# VFD_alpha_Sheet0.net
KiCad netlist of a schematic drawn in Altium Designer
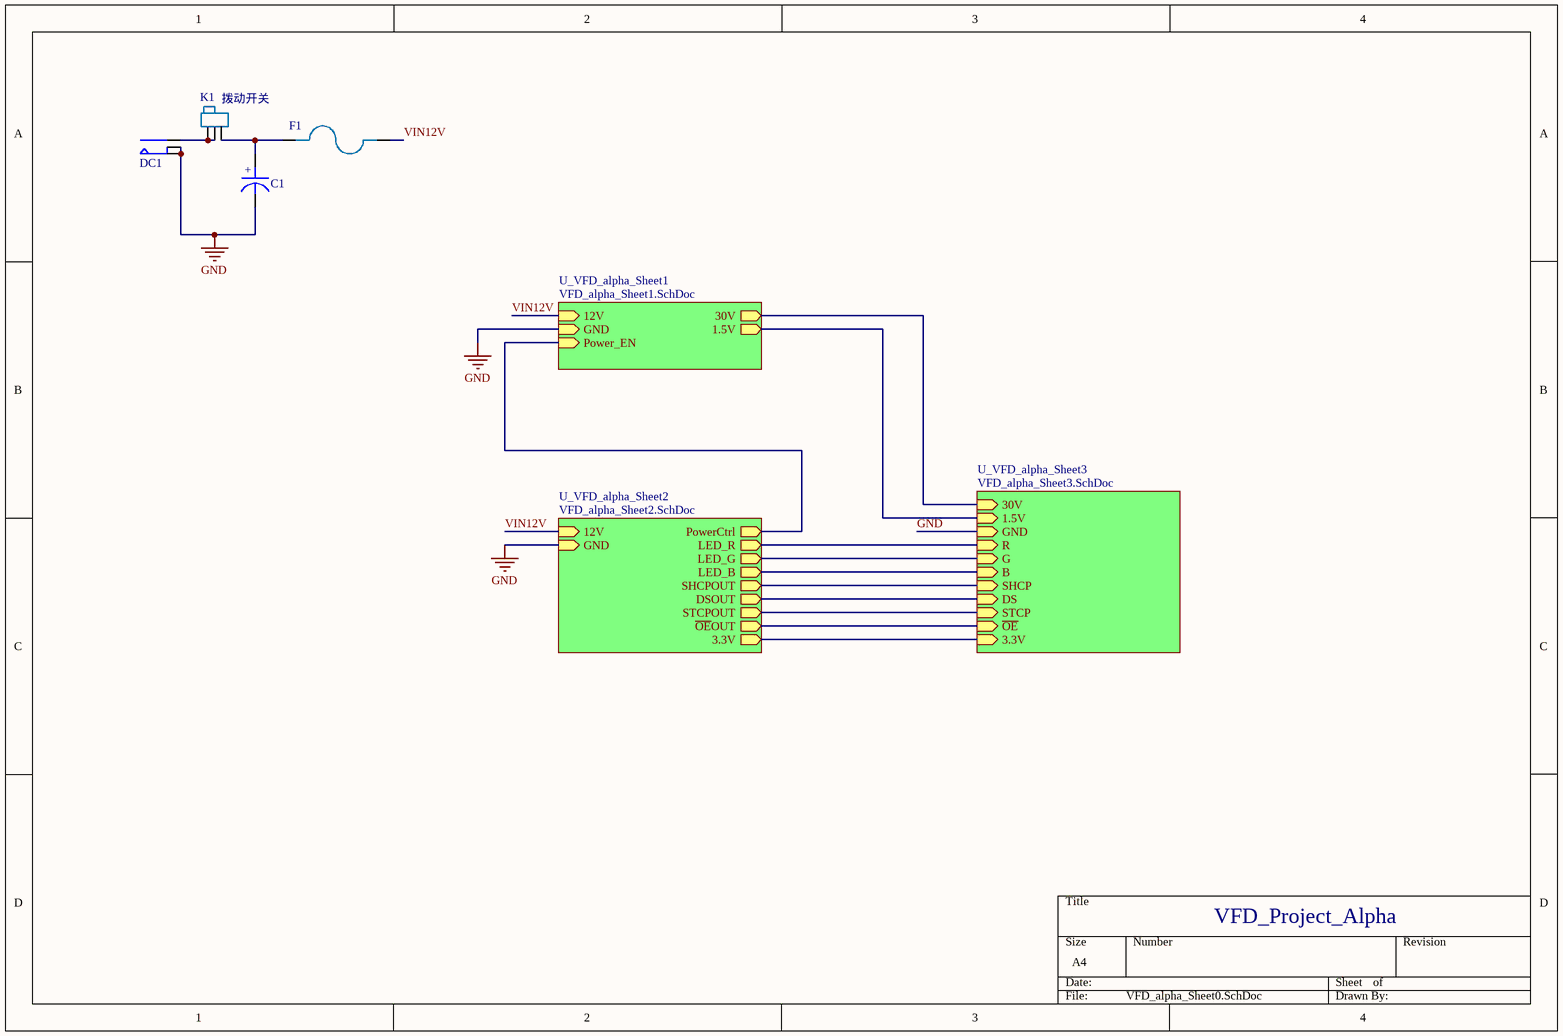
[diagram p0: VFD_alpha_Sheet0.SchDoc]

(export (version "E")
  (design (tool "Eeschema 10.0.6"))
  (components
    (comp (ref "C1") (value "CAP_D5") (footprint "CAP_5_2") (libsource (lib "ZZB_Lib") (part "CAP_D5")))
    (comp (ref "DC1") (value "DC-5.5") (footprint "DC5.5") (libsource (lib "ZZB_Lib") (part "DC-5.5")))
    (comp (ref "F1") (value "保险丝") (footprint "1812") (libsource (lib "ZZB_Lib") (part "保险丝")))
    (comp (ref "K1") (value "拨动开关") (footprint "拨动开关") (libsource (lib "ZZB_Lib") (part "拨动开关")))
  )
  (nets
    (net (code "11") (name "/VIN12V") (class "Default")
      (node (ref "F1") (pin "2") (pinfunction "2_2") (pintype "passive"))
    )
    (net (code "13") (name "GND") (class "Default")
      (node (ref "C1") (pin "2") (pinfunction "2_2") (pintype "passive"))
      (node (ref "DC1") (pin "2") (pinfunction "2_2") (pintype "passive"))
      (node (ref "DC1") (pin "3") (pinfunction "3_3") (pintype "passive"))
    )
    (net (code "14") (name "Net-(C1-Pad1)") (class "Default")
      (node (ref "C1") (pin "1") (pinfunction "1_1") (pintype "passive"))
      (node (ref "F1") (pin "1") (pinfunction "1_1") (pintype "passive"))
      (node (ref "K1") (pin "3") (pinfunction "3_3") (pintype "passive"))
    )
    (net (code "15") (name "Net-(DC1-Pad1)") (class "Default")
      (node (ref "DC1") (pin "1") (pinfunction "1_1") (pintype "passive"))
      (node (ref "K1") (pin "1") (pinfunction "1_1") (pintype "passive"))
      (node (ref "K1") (pin "2") (pinfunction "2_2") (pintype "passive"))
    )
  )
)
